# VOC_SensorBoard.net
KiCad netlist of a schematic drawn in EAGLE
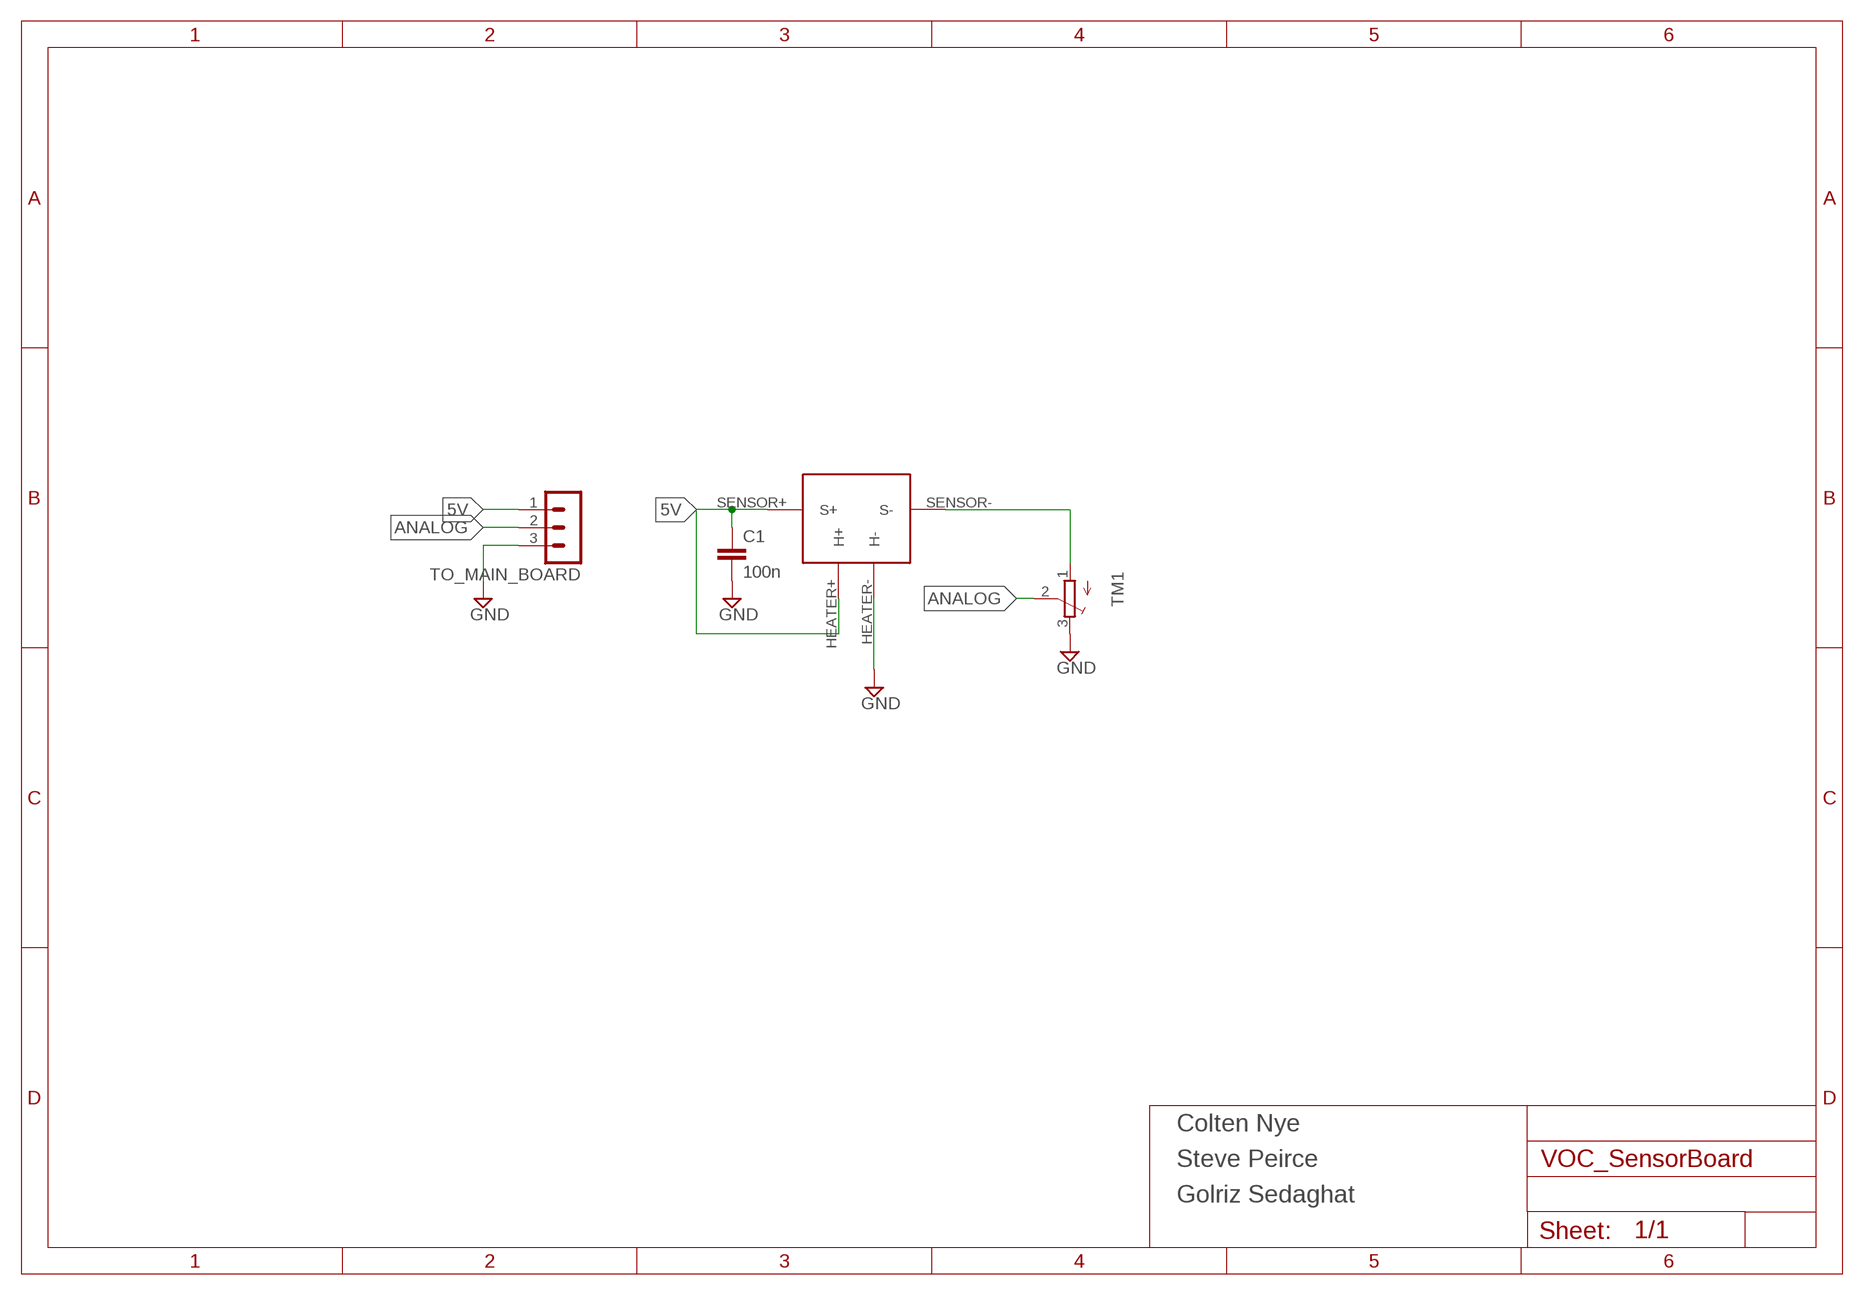
[diagram p0: schematic, sheet 1]

(export (version "E")
  (design (tool "Eeschema 10.0.6"))
  (components
    (comp (ref "C1")
      (value "100n")
      (footprint "eagle-import:C0805")
      (libsource (lib "eagle-import") (part "C-EUC0805"))
    )
    (comp (ref "TM1")
      (value "TRIMPOTTC33X")
      (footprint "eagle-import:TC33X")
      (libsource (lib "eagle-import") (part "TRIMPOTTC33X"))
    )
    (comp (ref "TO_MAIN_BOARD")
      (value "MA03-1")
      (footprint "eagle-import:MA03-1")
      (libsource (lib "eagle-import") (part "MA03-1"))
    )
    (comp (ref "U$1")
      (value "TGS2602")
      (footprint "eagle-import:TGS2602")
      (libsource (lib "eagle-import") (part "TGS2602"))
    )
  )
  (nets
    (net (code "1") (name "5V") (class "Default")
      (node (ref "C1") (pin "1") (pinfunction "1_1") (pintype "passive"))
      (node (ref "TO_MAIN_BOARD") (pin "1") (pinfunction "1_1") (pintype "passive"))
      (node (ref "U$1") (pin "HEATER+") (pinfunction "H+_HEATER+") (pintype "bidirectional"))
      (node (ref "U$1") (pin "SENSOR+") (pinfunction "S+_SENSOR+") (pintype "bidirectional"))
    )
    (net (code "2") (name "ANALOG") (class "Default")
      (node (ref "TM1") (pin "2") (pinfunction "S_2") (pintype "passive"))
      (node (ref "TO_MAIN_BOARD") (pin "2") (pinfunction "2_2") (pintype "passive"))
    )
    (net (code "3") (name "GND") (class "Default")
      (node (ref "C1") (pin "2") (pinfunction "2_2") (pintype "passive"))
      (node (ref "TM1") (pin "3") (pinfunction "E_3") (pintype "passive"))
      (node (ref "TO_MAIN_BOARD") (pin "3") (pinfunction "3_3") (pintype "passive"))
      (node (ref "U$1") (pin "HEATER-") (pinfunction "H-_HEATER-") (pintype "bidirectional"))
    )
    (net (code "4") (name "Net-(TM1-A)") (class "Default")
      (node (ref "TM1") (pin "1") (pinfunction "A_1") (pintype "passive"))
      (node (ref "U$1") (pin "SENSOR-") (pinfunction "S-_SENSOR-") (pintype "bidirectional"))
    )
  )
)
